# Schematic_Sheet1.net
KiCad netlist of a schematic drawn in Altium Designer
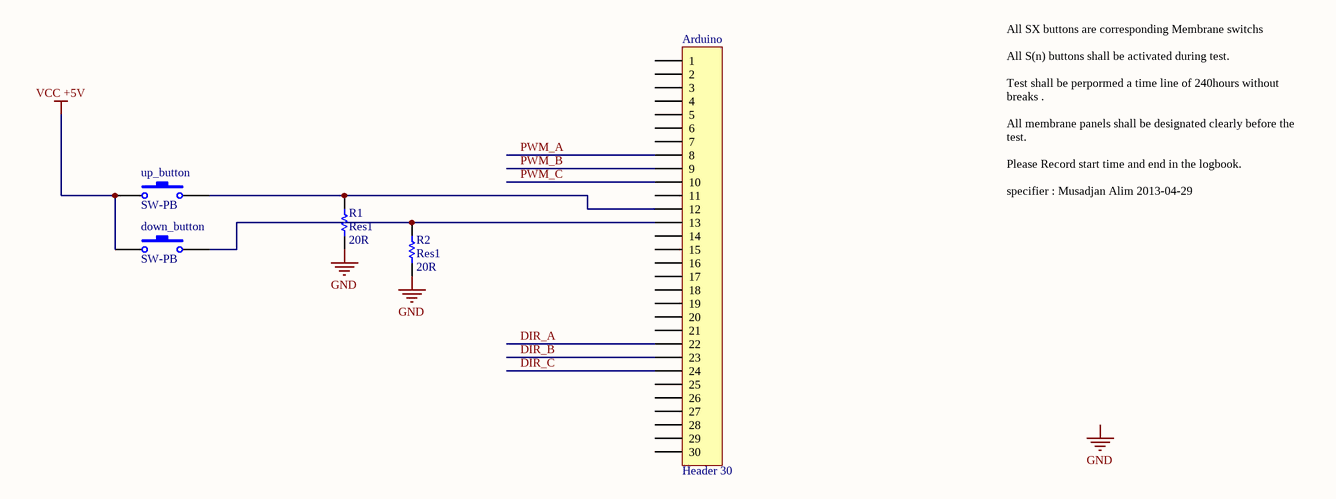
[diagram p0: Schematic Sheet1.SchDoc]

(export (version "E")
  (design (tool "Eeschema 10.0.6"))
  (components
    (comp (ref "Arduino")
      (value "Header 30")
      (footprint "HDR1X30")
      (description "Header, 30-Pin")
      (fields (field (name "PUBLISHER") "Altium Limited"))
      (libsource (lib "Miscellaneous Connectors") (part "Header 30"))
    )
    (comp (ref "down_button")
      (value "SW-PB")
      (footprint "SPST-2")
      (description "Switch")
      (fields (field (name "PUBLISHER") "Altium Limited"))
      (libsource (lib "Miscellaneous Devices") (part "SW-PB"))
    )
    (comp (ref "R1")
      (value "Res1")
      (footprint "AXIAL-0.3")
      (description "Resistor")
      (fields (field (name "ALTIUM_VALUE") "20R") (field (name "PUBLISHER") "Altium Limited"))
      (libsource (lib "Miscellaneous Devices") (part "Res1"))
    )
    (comp (ref "R2")
      (value "Res1")
      (footprint "AXIAL-0.3")
      (description "Resistor")
      (fields (field (name "ALTIUM_VALUE") "20R") (field (name "PUBLISHER") "Altium Limited"))
      (libsource (lib "Miscellaneous Devices") (part "Res1"))
    )
    (comp (ref "up_button")
      (value "SW-PB")
      (footprint "SPST-2")
      (description "Switch")
      (fields (field (name "PUBLISHER") "Altium Limited"))
      (libsource (lib "Miscellaneous Devices") (part "SW-PB"))
    )
  )
  (nets
    (net (code "1") (name "/DIR_A") (class "Default")
      (node (ref "Arduino") (pin "22") (pinfunction "22_22") (pintype "passive"))
    )
    (net (code "2") (name "/DIR_B") (class "Default")
      (node (ref "Arduino") (pin "23") (pinfunction "23_23") (pintype "passive"))
    )
    (net (code "3") (name "/DIR_C") (class "Default")
      (node (ref "Arduino") (pin "24") (pinfunction "24_24") (pintype "passive"))
    )
    (net (code "4") (name "/PWM_A") (class "Default")
      (node (ref "Arduino") (pin "8") (pinfunction "8_8") (pintype "passive"))
    )
    (net (code "5") (name "/PWM_B") (class "Default")
      (node (ref "Arduino") (pin "9") (pinfunction "9_9") (pintype "passive"))
    )
    (net (code "6") (name "/PWM_C") (class "Default")
      (node (ref "Arduino") (pin "10") (pinfunction "10_10") (pintype "passive"))
    )
    (net (code "7") (name "GND") (class "Default")
      (node (ref "R1") (pin "1") (pinfunction "1_1") (pintype "passive"))
      (node (ref "R2") (pin "1") (pinfunction "1_1") (pintype "passive"))
    )
    (net (code "8") (name "Net-(Arduino-Pad12)") (class "Default")
      (node (ref "Arduino") (pin "12") (pinfunction "12_12") (pintype "passive"))
      (node (ref "R1") (pin "2") (pinfunction "2_2") (pintype "passive"))
      (node (ref "up_button") (pin "2") (pinfunction "2_2") (pintype "passive"))
    )
    (net (code "9") (name "Net-(Arduino-Pad13)") (class "Default")
      (node (ref "Arduino") (pin "13") (pinfunction "13_13") (pintype "passive"))
      (node (ref "R2") (pin "2") (pinfunction "2_2") (pintype "passive"))
      (node (ref "down_button") (pin "2") (pinfunction "2_2") (pintype "passive"))
    )
    (net (code "10") (name "VCC +5V") (class "Default")
      (node (ref "down_button") (pin "1") (pinfunction "1_1") (pintype "passive"))
      (node (ref "up_button") (pin "1") (pinfunction "1_1") (pintype "passive"))
    )
    (net (code "11") (name "unconnected-(Arduino-Pad1)") (class "Default")
      (node (ref "Arduino") (pin "1") (pinfunction "1_1") (pintype "passive"))
    )
    (net (code "12") (name "unconnected-(Arduino-Pad2)") (class "Default")
      (node (ref "Arduino") (pin "2") (pinfunction "2_2") (pintype "passive"))
    )
    (net (code "13") (name "unconnected-(Arduino-Pad3)") (class "Default")
      (node (ref "Arduino") (pin "3") (pinfunction "3_3") (pintype "passive"))
    )
    (net (code "14") (name "unconnected-(Arduino-Pad4)") (class "Default")
      (node (ref "Arduino") (pin "4") (pinfunction "4_4") (pintype "passive"))
    )
    (net (code "15") (name "unconnected-(Arduino-Pad5)") (class "Default")
      (node (ref "Arduino") (pin "5") (pinfunction "5_5") (pintype "passive"))
    )
    (net (code "16") (name "unconnected-(Arduino-Pad6)") (class "Default")
      (node (ref "Arduino") (pin "6") (pinfunction "6_6") (pintype "passive"))
    )
    (net (code "17") (name "unconnected-(Arduino-Pad7)") (class "Default")
      (node (ref "Arduino") (pin "7") (pinfunction "7_7") (pintype "passive"))
    )
    (net (code "18") (name "unconnected-(Arduino-Pad11)") (class "Default")
      (node (ref "Arduino") (pin "11") (pinfunction "11_11") (pintype "passive"))
    )
    (net (code "19") (name "unconnected-(Arduino-Pad14)") (class "Default")
      (node (ref "Arduino") (pin "14") (pinfunction "14_14") (pintype "passive"))
    )
    (net (code "20") (name "unconnected-(Arduino-Pad15)") (class "Default")
      (node (ref "Arduino") (pin "15") (pinfunction "15_15") (pintype "passive"))
    )
    (net (code "21") (name "unconnected-(Arduino-Pad16)") (class "Default")
      (node (ref "Arduino") (pin "16") (pinfunction "16_16") (pintype "passive"))
    )
    (net (code "22") (name "unconnected-(Arduino-Pad17)") (class "Default")
      (node (ref "Arduino") (pin "17") (pinfunction "17_17") (pintype "passive"))
    )
    (net (code "23") (name "unconnected-(Arduino-Pad18)") (class "Default")
      (node (ref "Arduino") (pin "18") (pinfunction "18_18") (pintype "passive"))
    )
    (net (code "24") (name "unconnected-(Arduino-Pad19)") (class "Default")
      (node (ref "Arduino") (pin "19") (pinfunction "19_19") (pintype "passive"))
    )
    (net (code "25") (name "unconnected-(Arduino-Pad20)") (class "Default")
      (node (ref "Arduino") (pin "20") (pinfunction "20_20") (pintype "passive"))
    )
    (net (code "26") (name "unconnected-(Arduino-Pad21)") (class "Default")
      (node (ref "Arduino") (pin "21") (pinfunction "21_21") (pintype "passive"))
    )
    (net (code "27") (name "unconnected-(Arduino-Pad25)") (class "Default")
      (node (ref "Arduino") (pin "25") (pinfunction "25_25") (pintype "passive"))
    )
    (net (code "28") (name "unconnected-(Arduino-Pad26)") (class "Default")
      (node (ref "Arduino") (pin "26") (pinfunction "26_26") (pintype "passive"))
    )
    (net (code "29") (name "unconnected-(Arduino-Pad27)") (class "Default")
      (node (ref "Arduino") (pin "27") (pinfunction "27_27") (pintype "passive"))
    )
    (net (code "30") (name "unconnected-(Arduino-Pad28)") (class "Default")
      (node (ref "Arduino") (pin "28") (pinfunction "28_28") (pintype "passive"))
    )
    (net (code "31") (name "unconnected-(Arduino-Pad29)") (class "Default")
      (node (ref "Arduino") (pin "29") (pinfunction "29_29") (pintype "passive"))
    )
    (net (code "32") (name "unconnected-(Arduino-Pad30)") (class "Default")
      (node (ref "Arduino") (pin "30") (pinfunction "30_30") (pintype "passive"))
    )
  )
)
